# Bucks.net
KiCad netlist of a schematic drawn in Altium Designer
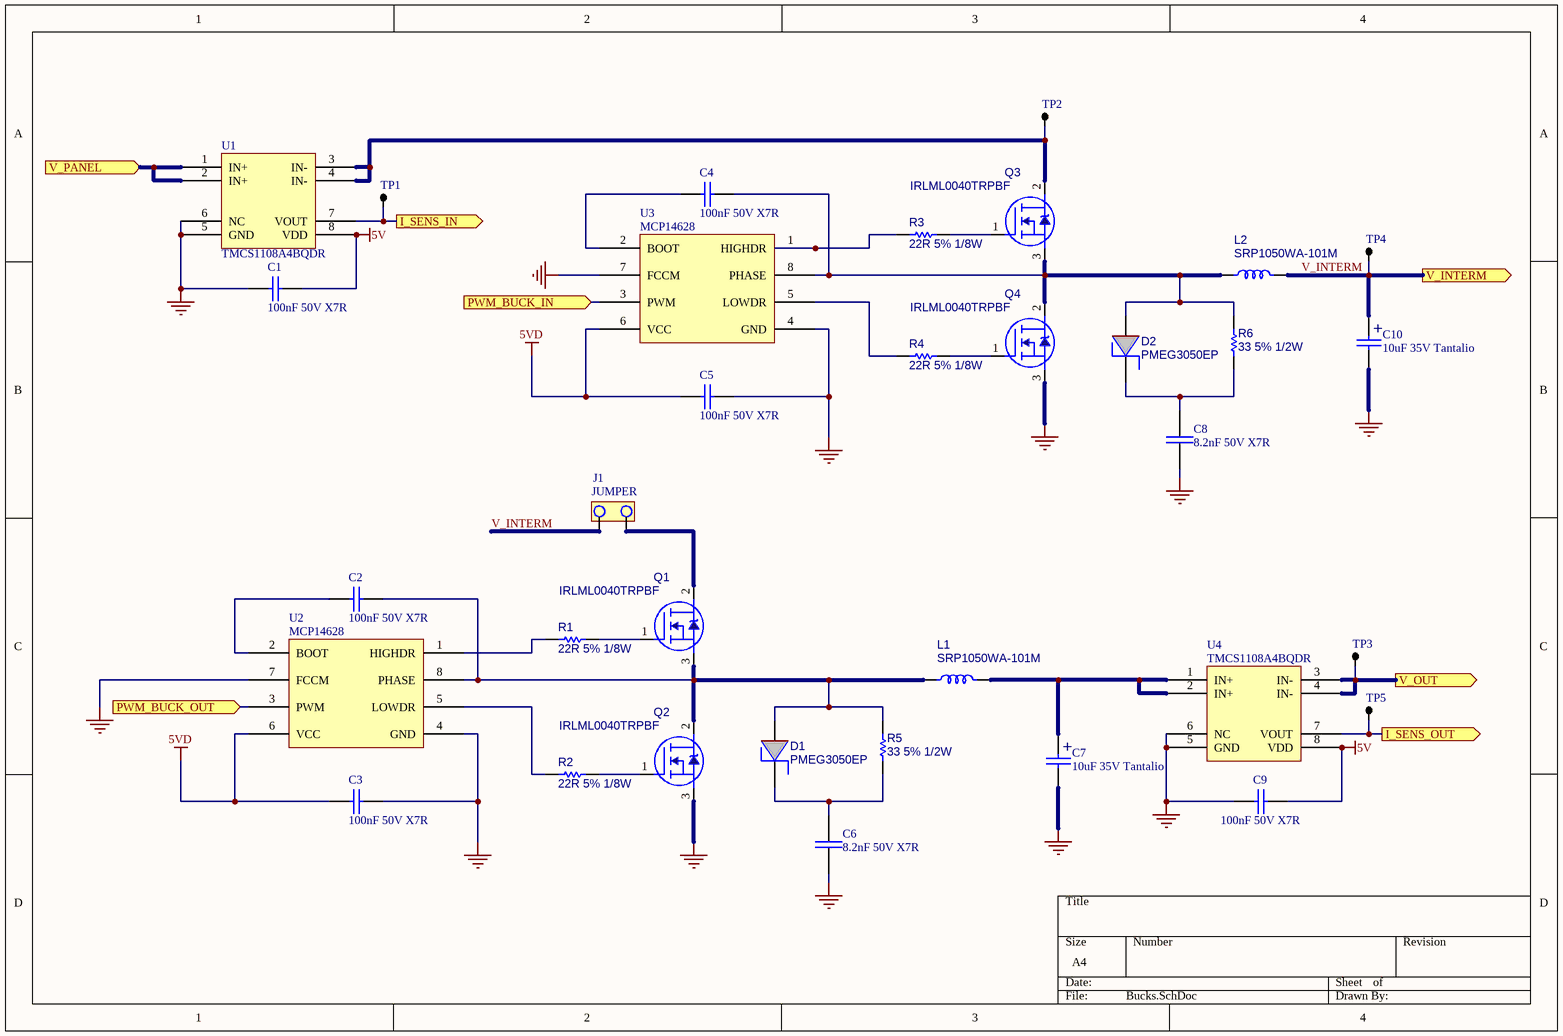
[diagram p0: Bucks.SchDoc]

(export (version "E")
  (design (tool "Eeschema 10.0.6"))
  (components
    (comp (ref "C1")
      (value "100nF 50V X7R")
      (footprint "0805")
      (libsource (lib "Libreria_Casera") (part "CAP"))
    )
    (comp (ref "C2")
      (value "100nF 50V X7R")
      (footprint "0805")
      (libsource (lib "Libreria_Casera") (part "CAP"))
    )
    (comp (ref "C3")
      (value "100nF 50V X7R")
      (footprint "0805")
      (libsource (lib "Libreria_Casera") (part "CAP"))
    )
    (comp (ref "C4")
      (value "100nF 50V X7R")
      (footprint "0805")
      (libsource (lib "Libreria_Casera") (part "CAP"))
    )
    (comp (ref "C5")
      (value "100nF 50V X7R")
      (footprint "0805")
      (libsource (lib "Libreria_Casera") (part "CAP"))
    )
    (comp (ref "C6")
      (value "8.2nF 50V X7R")
      (footprint "0805")
      (description "Ceramic Capacitor")
      (libsource (lib "MPPTLib") (part "Ceramic capacitor"))
    )
    (comp (ref "C7")
      (value "10uF 35V Tantalio")
      (footprint "CAPPOL1210")
      (description "TCJB106M035R0200")
      (libsource (lib "Libreria_Casera") (part "CAPPOL"))
    )
    (comp (ref "C8")
      (value "8.2nF 50V X7R")
      (footprint "0805")
      (description "Ceramic Capacitor")
      (libsource (lib "MPPTLib") (part "Ceramic capacitor"))
    )
    (comp (ref "C9")
      (value "100nF 50V X7R")
      (footprint "0805")
      (libsource (lib "Libreria_Casera") (part "CAP"))
    )
    (comp (ref "C10")
      (value "10uF 35V Tantalio")
      (footprint "CAPPOL1210")
      (description "TCJB106M035R0200")
      (libsource (lib "Libreria_Casera") (part "CAPPOL"))
    )
    (comp (ref "D1")
      (value "PMEG3050EP")
      (footprint "SOD-128")
      (description "Diode Shottky")
      (libsource (lib "MPPTLib") (part "DIODO_SH"))
    )
    (comp (ref "D2")
      (value "PMEG3050EP")
      (footprint "SOD-128")
      (description "Diode Shottky")
      (libsource (lib "MPPTLib") (part "DIODO_SH"))
    )
    (comp (ref "J1") (value "JUMPER") (footprint "0805") (libsource (lib "Libreria_Casera") (part "JUMPER")))
    (comp (ref "L1")
      (value "SRP1050WA-101M")
      (footprint "SRP1050WA")
      (description "Inductor")
      (libsource (lib "MPPTLib") (part "IND"))
    )
    (comp (ref "L2")
      (value "SRP1050WA-101M")
      (footprint "SRP1050WA")
      (description "Inductor")
      (libsource (lib "MPPTLib") (part "IND"))
    )
    (comp (ref "Q1")
      (value "IRLML0040TRPBF")
      (footprint "DPAK")
      (description "Mosfet N-Ch")
      (libsource (lib "MPPTLib") (part "N_MOSFET_SOT23"))
    )
    (comp (ref "Q2")
      (value "IRLML0040TRPBF")
      (footprint "DPAK")
      (description "Mosfet N-Ch")
      (libsource (lib "MPPTLib") (part "N_MOSFET_SOT23"))
    )
    (comp (ref "Q3")
      (value "IRLML0040TRPBF")
      (footprint "DPAK")
      (description "Mosfet N-Ch")
      (libsource (lib "MPPTLib") (part "N_MOSFET_SOT23"))
    )
    (comp (ref "Q4")
      (value "IRLML0040TRPBF")
      (footprint "DPAK")
      (description "Mosfet N-Ch")
      (libsource (lib "MPPTLib") (part "N_MOSFET_SOT23"))
    )
    (comp (ref "R1")
      (value "22R 5% 1/8W")
      (footprint "0805")
      (description "Resistor")
      (libsource (lib "MPPTLib") (part "Res1"))
    )
    (comp (ref "R2")
      (value "22R 5% 1/8W")
      (footprint "0805")
      (description "Resistor")
      (libsource (lib "MPPTLib") (part "Res1"))
    )
    (comp (ref "R3")
      (value "22R 5% 1/8W")
      (footprint "0805")
      (description "Resistor")
      (libsource (lib "MPPTLib") (part "Res1"))
    )
    (comp (ref "R4")
      (value "22R 5% 1/8W")
      (footprint "0805")
      (description "Resistor")
      (libsource (lib "MPPTLib") (part "Res1"))
    )
    (comp (ref "R5")
      (value "33 5% 1/2W")
      (footprint "1206")
      (description "Resistor")
      (libsource (lib "MPPTLib") (part "Res1"))
    )
    (comp (ref "R6")
      (value "33 5% 1/2W")
      (footprint "1206")
      (description "Resistor")
      (libsource (lib "MPPTLib") (part "Res1"))
    )
    (comp (ref "TP1") (value "TP") (footprint "TP_COMPACT") (libsource (lib "Libreria_Casera") (part "TP")))
    (comp (ref "TP2") (value "TP") (footprint "TP_COMPACT") (libsource (lib "Libreria_Casera") (part "TP")))
    (comp (ref "TP3") (value "TP") (footprint "TP_COMPACT") (libsource (lib "Libreria_Casera") (part "TP")))
    (comp (ref "TP4") (value "TP") (footprint "TP_COMPACT") (libsource (lib "Libreria_Casera") (part "TP")))
    (comp (ref "TP5") (value "TP") (footprint "TP_COMPACT") (libsource (lib "Libreria_Casera") (part "TP")))
    (comp (ref "U1")
      (value "TMCS1108A4BQDR")
      (footprint "SO8")
      (libsource (lib "Libreria_Casera") (part "TMCS1108"))
    )
    (comp (ref "U2") (value "MCP14628") (footprint "SO8") (libsource (lib "MPPTLib") (part "MCP14628")))
    (comp (ref "U3") (value "MCP14628") (footprint "SO8") (libsource (lib "MPPTLib") (part "MCP14628")))
    (comp (ref "U4")
      (value "TMCS1108A4BQDR")
      (footprint "SO8")
      (libsource (lib "Libreria_Casera") (part "TMCS1108"))
    )
  )
  (nets
    (net (code "1") (name "/I_SENS_IN") (class "Default")
      (node (ref "TP1") (pin "1") (pinfunction "1_1") (pintype "passive"))
      (node (ref "U1") (pin "7") (pinfunction "VOUT_7") (pintype "passive"))
    )
    (net (code "2") (name "/I_SENS_OUT") (class "Default")
      (node (ref "TP5") (pin "1") (pinfunction "1_1") (pintype "passive"))
      (node (ref "U4") (pin "7") (pinfunction "VOUT_7") (pintype "passive"))
    )
    (net (code "3") (name "/PWM_BUCK_IN") (class "Default")
      (node (ref "U3") (pin "3") (pinfunction "PWM_3") (pintype "passive"))
    )
    (net (code "4") (name "/PWM_BUCK_OUT") (class "Default")
      (node (ref "U2") (pin "3") (pinfunction "PWM_3") (pintype "passive"))
    )
    (net (code "5") (name "/V_INTERM") (class "Default")
      (node (ref "C10") (pin "1") (pinfunction "1_1") (pintype "passive"))
      (node (ref "J1") (pin "2") (pinfunction "2_2") (pintype "passive"))
      (node (ref "L2") (pin "2") (pinfunction "2_2") (pintype "passive"))
      (node (ref "TP4") (pin "1") (pinfunction "1_1") (pintype "passive"))
    )
    (net (code "6") (name "/V_OUT") (class "Default")
      (node (ref "TP3") (pin "1") (pinfunction "1_1") (pintype "passive"))
      (node (ref "U4") (pin "3") (pinfunction "IN-_3") (pintype "passive"))
      (node (ref "U4") (pin "4") (pinfunction "IN-_4") (pintype "passive"))
    )
    (net (code "7") (name "/V_PANEL") (class "Default")
      (node (ref "U1") (pin "1") (pinfunction "IN+_1") (pintype "passive"))
      (node (ref "U1") (pin "2") (pinfunction "IN+_2") (pintype "passive"))
    )
    (net (code "8") (name "5V") (class "Default")
      (node (ref "C1") (pin "1") (pinfunction "1_1") (pintype "passive"))
      (node (ref "C9") (pin "1") (pinfunction "1_1") (pintype "passive"))
      (node (ref "U1") (pin "8") (pinfunction "VDD_8") (pintype "passive"))
      (node (ref "U4") (pin "8") (pinfunction "VDD_8") (pintype "passive"))
    )
    (net (code "9") (name "5VD") (class "Default")
      (node (ref "C3") (pin "2") (pinfunction "2_2") (pintype "passive"))
      (node (ref "C5") (pin "2") (pinfunction "2_2") (pintype "passive"))
      (node (ref "U2") (pin "6") (pinfunction "VCC_6") (pintype "passive"))
      (node (ref "U3") (pin "6") (pinfunction "VCC_6") (pintype "passive"))
    )
    (net (code "10") (name "GND") (class "Default")
      (node (ref "C1") (pin "2") (pinfunction "2_2") (pintype "passive"))
      (node (ref "C10") (pin "2") (pinfunction "2_2") (pintype "passive"))
      (node (ref "C3") (pin "1") (pinfunction "1_1") (pintype "passive"))
      (node (ref "C5") (pin "1") (pinfunction "1_1") (pintype "passive"))
      (node (ref "C6") (pin "2") (pinfunction "2_2") (pintype "passive"))
      (node (ref "C7") (pin "2") (pinfunction "2_2") (pintype "passive"))
      (node (ref "C8") (pin "2") (pinfunction "2_2") (pintype "passive"))
      (node (ref "C9") (pin "2") (pinfunction "2_2") (pintype "passive"))
      (node (ref "Q2") (pin "3") (pinfunction "SOURCE_3") (pintype "passive"))
      (node (ref "Q4") (pin "3") (pinfunction "SOURCE_3") (pintype "passive"))
      (node (ref "U1") (pin "5") (pinfunction "GND_5") (pintype "passive"))
      (node (ref "U1") (pin "6") (pinfunction "NC_6") (pintype "passive"))
      (node (ref "U2") (pin "4") (pinfunction "GND_4") (pintype "passive"))
      (node (ref "U2") (pin "7") (pinfunction "FCCM_7") (pintype "passive"))
      (node (ref "U3") (pin "4") (pinfunction "GND_4") (pintype "passive"))
      (node (ref "U3") (pin "7") (pinfunction "FCCM_7") (pintype "passive"))
      (node (ref "U4") (pin "5") (pinfunction "GND_5") (pintype "passive"))
      (node (ref "U4") (pin "6") (pinfunction "NC_6") (pintype "passive"))
    )
    (net (code "11") (name "Net-(C7-Pad1)") (class "Default")
      (node (ref "C7") (pin "1") (pinfunction "1_1") (pintype "passive"))
      (node (ref "L1") (pin "2") (pinfunction "2_2") (pintype "passive"))
      (node (ref "U4") (pin "1") (pinfunction "IN+_1") (pintype "passive"))
      (node (ref "U4") (pin "2") (pinfunction "IN+_2") (pintype "passive"))
    )
    (net (code "12") (name "Net-(D1-A)") (class "Default")
      (node (ref "C2") (pin "1") (pinfunction "1_1") (pintype "passive"))
      (node (ref "D1") (pin "1") (pinfunction "A_1") (pintype "passive"))
      (node (ref "L1") (pin "1") (pinfunction "1_1") (pintype "passive"))
      (node (ref "Q1") (pin "3") (pinfunction "SOURCE_3") (pintype "passive"))
      (node (ref "Q2") (pin "2") (pinfunction "DRAIN_2") (pintype "passive"))
      (node (ref "R5") (pin "2") (pinfunction "2_2") (pintype "passive"))
      (node (ref "U2") (pin "8") (pinfunction "PHASE_8") (pintype "passive"))
    )
    (net (code "13") (name "Net-(D1-K)") (class "Default")
      (node (ref "C6") (pin "1") (pinfunction "1_1") (pintype "passive"))
      (node (ref "D1") (pin "2") (pinfunction "K_2") (pintype "passive"))
      (node (ref "R5") (pin "1") (pinfunction "1_1") (pintype "passive"))
    )
    (net (code "14") (name "Net-(D2-A)") (class "Default")
      (node (ref "C4") (pin "1") (pinfunction "1_1") (pintype "passive"))
      (node (ref "D2") (pin "1") (pinfunction "A_1") (pintype "passive"))
      (node (ref "L2") (pin "1") (pinfunction "1_1") (pintype "passive"))
      (node (ref "Q3") (pin "3") (pinfunction "SOURCE_3") (pintype "passive"))
      (node (ref "Q4") (pin "2") (pinfunction "DRAIN_2") (pintype "passive"))
      (node (ref "R6") (pin "2") (pinfunction "2_2") (pintype "passive"))
      (node (ref "U3") (pin "8") (pinfunction "PHASE_8") (pintype "passive"))
    )
    (net (code "15") (name "Net-(D2-K)") (class "Default")
      (node (ref "C8") (pin "1") (pinfunction "1_1") (pintype "passive"))
      (node (ref "D2") (pin "2") (pinfunction "K_2") (pintype "passive"))
      (node (ref "R6") (pin "1") (pinfunction "1_1") (pintype "passive"))
    )
    (net (code "16") (name "Net-(Q1-DRAIN)") (class "Default")
      (node (ref "J1") (pin "1") (pinfunction "1_1") (pintype "passive"))
      (node (ref "Q1") (pin "2") (pinfunction "DRAIN_2") (pintype "passive"))
    )
    (net (code "17") (name "Net-(Q1-GATE)") (class "Default")
      (node (ref "Q1") (pin "1") (pinfunction "GATE_1") (pintype "passive"))
      (node (ref "R1") (pin "1") (pinfunction "1_1") (pintype "passive"))
    )
    (net (code "18") (name "Net-(Q2-GATE)") (class "Default")
      (node (ref "Q2") (pin "1") (pinfunction "GATE_1") (pintype "passive"))
      (node (ref "R2") (pin "1") (pinfunction "1_1") (pintype "passive"))
    )
    (net (code "19") (name "Net-(Q3-DRAIN)") (class "Default")
      (node (ref "Q3") (pin "2") (pinfunction "DRAIN_2") (pintype "passive"))
      (node (ref "TP2") (pin "1") (pinfunction "1_1") (pintype "passive"))
      (node (ref "U1") (pin "3") (pinfunction "IN-_3") (pintype "passive"))
      (node (ref "U1") (pin "4") (pinfunction "IN-_4") (pintype "passive"))
    )
    (net (code "20") (name "Net-(Q3-GATE)") (class "Default")
      (node (ref "Q3") (pin "1") (pinfunction "GATE_1") (pintype "passive"))
      (node (ref "R3") (pin "1") (pinfunction "1_1") (pintype "passive"))
    )
    (net (code "21") (name "Net-(Q4-GATE)") (class "Default")
      (node (ref "Q4") (pin "1") (pinfunction "GATE_1") (pintype "passive"))
      (node (ref "R4") (pin "1") (pinfunction "1_1") (pintype "passive"))
    )
    (net (code "22") (name "Net-(U2-BOOT)") (class "Default")
      (node (ref "C2") (pin "2") (pinfunction "2_2") (pintype "passive"))
      (node (ref "U2") (pin "2") (pinfunction "BOOT_2") (pintype "passive"))
    )
    (net (code "23") (name "Net-(U2-HIGHDR)") (class "Default")
      (node (ref "R1") (pin "2") (pinfunction "2_2") (pintype "passive"))
      (node (ref "U2") (pin "1") (pinfunction "HIGHDR_1") (pintype "passive"))
    )
    (net (code "24") (name "Net-(U2-LOWDR)") (class "Default")
      (node (ref "R2") (pin "2") (pinfunction "2_2") (pintype "passive"))
      (node (ref "U2") (pin "5") (pinfunction "LOWDR_5") (pintype "passive"))
    )
    (net (code "25") (name "Net-(U3-BOOT)") (class "Default")
      (node (ref "C4") (pin "2") (pinfunction "2_2") (pintype "passive"))
      (node (ref "U3") (pin "2") (pinfunction "BOOT_2") (pintype "passive"))
    )
    (net (code "26") (name "Net-(U3-HIGHDR)") (class "Default")
      (node (ref "R3") (pin "2") (pinfunction "2_2") (pintype "passive"))
      (node (ref "U3") (pin "1") (pinfunction "HIGHDR_1") (pintype "passive"))
    )
    (net (code "27") (name "Net-(U3-LOWDR)") (class "Default")
      (node (ref "R4") (pin "2") (pinfunction "2_2") (pintype "passive"))
      (node (ref "U3") (pin "5") (pinfunction "LOWDR_5") (pintype "passive"))
    )
  )
)
